# timer.net
KiCad netlist of a schematic drawn in EAGLE
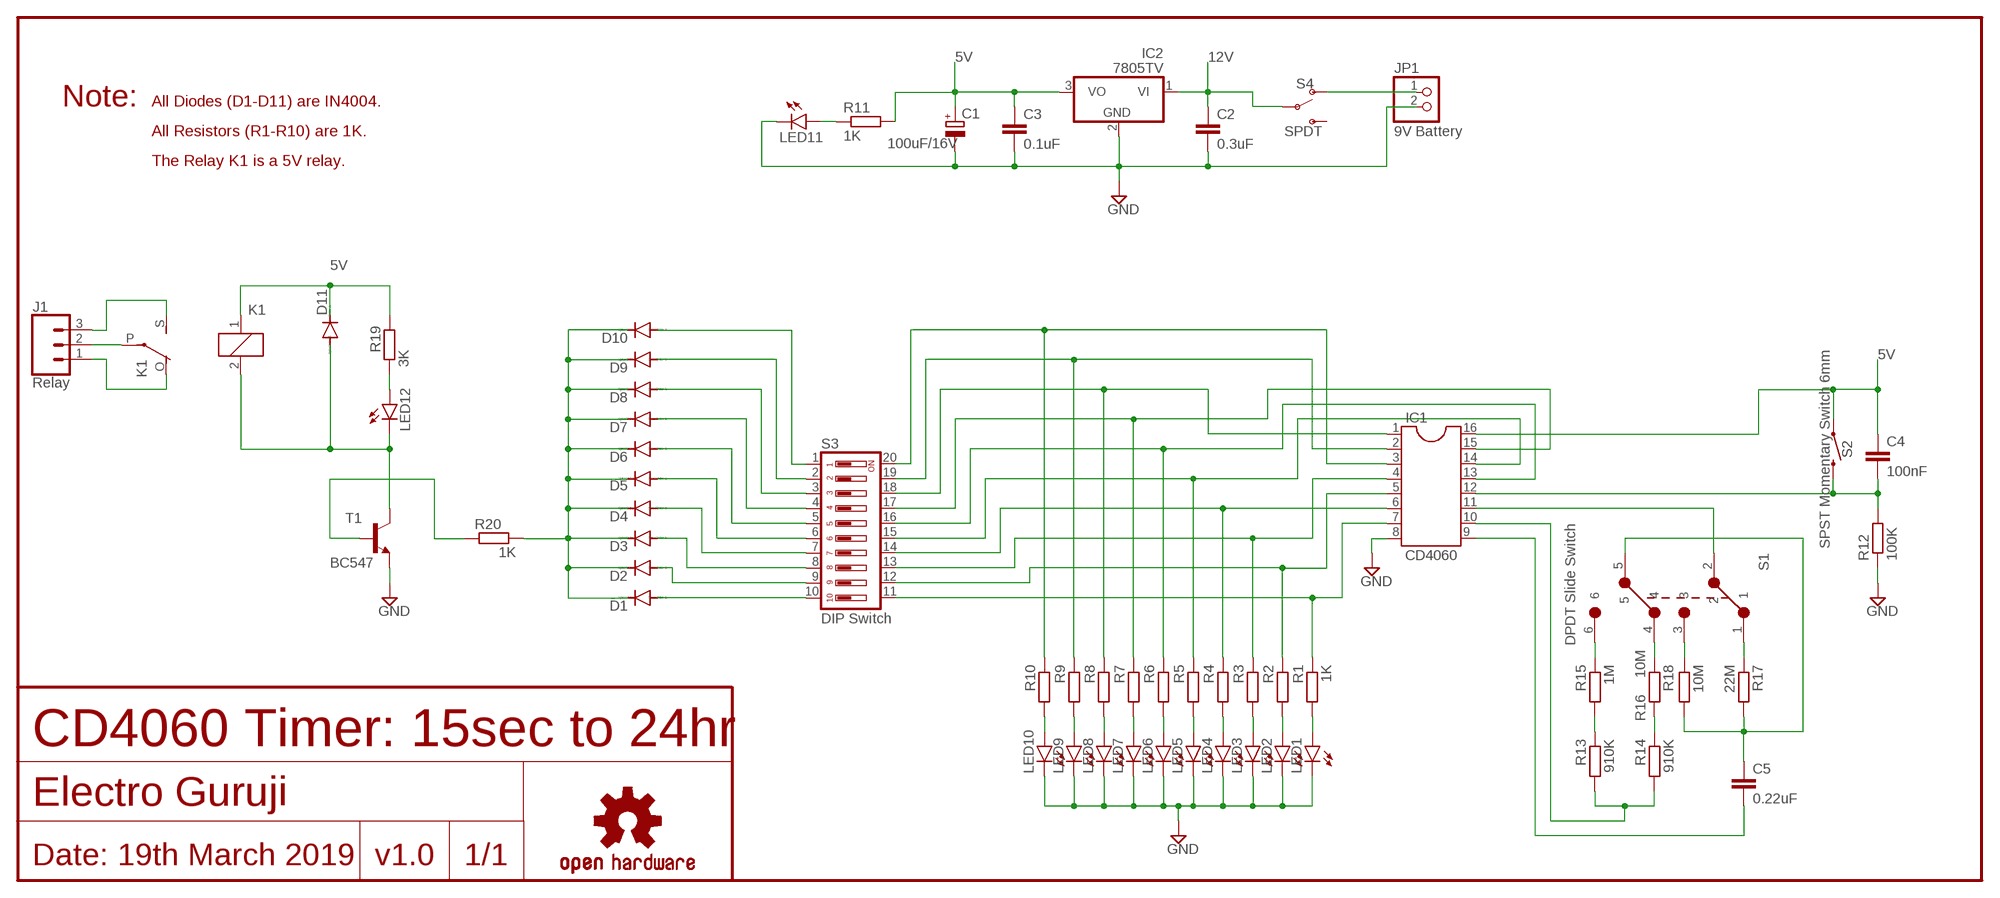
[diagram p0: schematic, sheet 1]

(export (version "E")
  (design (tool "Eeschema 10.0.6"))
  (components
    (comp (ref "C1")
      (value "100uF/16V")
      (footprint "eagle-import:E2,5-6")
      (libsource (lib "eagle-import") (part "CPOL-EUE2.5-6"))
    )
    (comp (ref "C2")
      (value "0.3uF")
      (footprint "eagle-import:C025-050X050")
      (libsource (lib "eagle-import") (part "C-EU025-050X050"))
    )
    (comp (ref "C3")
      (value "0.1uF")
      (footprint "eagle-import:C025-050X050")
      (libsource (lib "eagle-import") (part "C-EU025-050X050"))
    )
    (comp (ref "C4")
      (value "100nF")
      (footprint "eagle-import:C025-050X050")
      (libsource (lib "eagle-import") (part "C-EU025-050X050"))
    )
    (comp (ref "C5")
      (value "0.22uF")
      (footprint "eagle-import:C102-043X133")
      (libsource (lib "eagle-import") (part "C-EU102-043X133"))
    )
    (comp (ref "D1")
      (value "1N4004")
      (footprint "eagle-import:DO41-10")
      (libsource (lib "eagle-import") (part "1N4004"))
    )
    (comp (ref "D2")
      (value "1N4004")
      (footprint "eagle-import:DO41-10")
      (libsource (lib "eagle-import") (part "1N4004"))
    )
    (comp (ref "D3")
      (value "1N4004")
      (footprint "eagle-import:DO41-10")
      (libsource (lib "eagle-import") (part "1N4004"))
    )
    (comp (ref "D4")
      (value "1N4004")
      (footprint "eagle-import:DO41-10")
      (libsource (lib "eagle-import") (part "1N4004"))
    )
    (comp (ref "D5")
      (value "1N4004")
      (footprint "eagle-import:DO41-10")
      (libsource (lib "eagle-import") (part "1N4004"))
    )
    (comp (ref "D6")
      (value "1N4004")
      (footprint "eagle-import:DO41-10")
      (libsource (lib "eagle-import") (part "1N4004"))
    )
    (comp (ref "D7")
      (value "1N4004")
      (footprint "eagle-import:DO41-10")
      (libsource (lib "eagle-import") (part "1N4004"))
    )
    (comp (ref "D8")
      (value "1N4004")
      (footprint "eagle-import:DO41-10")
      (libsource (lib "eagle-import") (part "1N4004"))
    )
    (comp (ref "D9")
      (value "1N4004")
      (footprint "eagle-import:DO41-10")
      (libsource (lib "eagle-import") (part "1N4004"))
    )
    (comp (ref "D10")
      (value "1N4004")
      (footprint "eagle-import:DO41-10")
      (libsource (lib "eagle-import") (part "1N4004"))
    )
    (comp (ref "D11")
      (value "1N4004")
      (footprint "eagle-import:DO41-10")
      (libsource (lib "eagle-import") (part "1N4004"))
    )
    (comp (ref "IC1")
      (value "CD4060")
      (footprint "eagle-import:SOCKET-16")
      (libsource (lib "eagle-import") (part "DIL16S"))
    )
    (comp (ref "IC2")
      (value "7805TV")
      (footprint "eagle-import:TO220V")
      (libsource (lib "eagle-import") (part "78TV05"))
    )
    (comp (ref "J1")
      (value "Relay")
      (footprint "eagle-import:SCREWTERMINAL-5MM-3")
      (libsource (lib "eagle-import") (part "CONN_03-SCREW-5MM"))
    )
    (comp (ref "JP1")
      (value "9V Battery")
      (footprint "eagle-import:1X02")
      (libsource (lib "eagle-import") (part "PINHD-1X2"))
    )
    (comp (ref "K1")
      (value "5V")
      (footprint "eagle-import:ZF112")
      (libsource (lib "eagle-import") (part "ZF112"))
    )
    (comp (ref "LED1")
      (value "LED5MM")
      (footprint "eagle-import:LED5MM")
      (libsource (lib "eagle-import") (part "LED5MM"))
    )
    (comp (ref "LED2")
      (value "LED5MM")
      (footprint "eagle-import:LED5MM")
      (libsource (lib "eagle-import") (part "LED5MM"))
    )
    (comp (ref "LED3")
      (value "LED5MM")
      (footprint "eagle-import:LED5MM")
      (libsource (lib "eagle-import") (part "LED5MM"))
    )
    (comp (ref "LED4")
      (value "LED5MM")
      (footprint "eagle-import:LED5MM")
      (libsource (lib "eagle-import") (part "LED5MM"))
    )
    (comp (ref "LED5")
      (value "LED5MM")
      (footprint "eagle-import:LED5MM")
      (libsource (lib "eagle-import") (part "LED5MM"))
    )
    (comp (ref "LED6")
      (value "LED5MM")
      (footprint "eagle-import:LED5MM")
      (libsource (lib "eagle-import") (part "LED5MM"))
    )
    (comp (ref "LED7")
      (value "LED5MM")
      (footprint "eagle-import:LED5MM")
      (libsource (lib "eagle-import") (part "LED5MM"))
    )
    (comp (ref "LED8")
      (value "LED5MM")
      (footprint "eagle-import:LED5MM")
      (libsource (lib "eagle-import") (part "LED5MM"))
    )
    (comp (ref "LED9")
      (value "LED5MM")
      (footprint "eagle-import:LED5MM")
      (libsource (lib "eagle-import") (part "LED5MM"))
    )
    (comp (ref "LED10")
      (value "LED5MM")
      (footprint "eagle-import:LED5MM")
      (libsource (lib "eagle-import") (part "LED5MM"))
    )
    (comp (ref "LED11")
      (value "LED5MM")
      (footprint "eagle-import:LED5MM")
      (libsource (lib "eagle-import") (part "LED5MM"))
    )
    (comp (ref "LED12")
      (value "LED5MM")
      (footprint "eagle-import:LED5MM")
      (libsource (lib "eagle-import") (part "LED5MM"))
    )
    (comp (ref "LOGO1")
      (value "OSHW-LOGOS-COPPER")
      (footprint "eagle-import:OSHW-LOGO-S_COPPER")
      (libsource (lib "eagle-import") (part "OSHW-LOGOS-COPPER"))
    )
    (comp (ref "R1")
      (value "1K")
      (footprint "eagle-import:0207_10")
      (libsource (lib "eagle-import") (part "R-EU_0207/10"))
    )
    (comp (ref "R2")
      (value "R-EU_0207/10")
      (footprint "eagle-import:0207_10")
      (libsource (lib "eagle-import") (part "R-EU_0207/10"))
    )
    (comp (ref "R3")
      (value "R-EU_0207/10")
      (footprint "eagle-import:0207_10")
      (libsource (lib "eagle-import") (part "R-EU_0207/10"))
    )
    (comp (ref "R4")
      (value "R-EU_0207/10")
      (footprint "eagle-import:0207_10")
      (libsource (lib "eagle-import") (part "R-EU_0207/10"))
    )
    (comp (ref "R5")
      (value "R-EU_0207/10")
      (footprint "eagle-import:0207_10")
      (libsource (lib "eagle-import") (part "R-EU_0207/10"))
    )
    (comp (ref "R6")
      (value "R-EU_0207/10")
      (footprint "eagle-import:0207_10")
      (libsource (lib "eagle-import") (part "R-EU_0207/10"))
    )
    (comp (ref "R7")
      (value "R-EU_0207/10")
      (footprint "eagle-import:0207_10")
      (libsource (lib "eagle-import") (part "R-EU_0207/10"))
    )
    (comp (ref "R8")
      (value "R-EU_0207/10")
      (footprint "eagle-import:0207_10")
      (libsource (lib "eagle-import") (part "R-EU_0207/10"))
    )
    (comp (ref "R9")
      (value "R-EU_0207/10")
      (footprint "eagle-import:0207_10")
      (libsource (lib "eagle-import") (part "R-EU_0207/10"))
    )
    (comp (ref "R10")
      (value "R-EU_0207/10")
      (footprint "eagle-import:0207_10")
      (libsource (lib "eagle-import") (part "R-EU_0207/10"))
    )
    (comp (ref "R11")
      (value "1K")
      (footprint "eagle-import:0207_10")
      (libsource (lib "eagle-import") (part "R-EU_0207/10"))
    )
    (comp (ref "R12")
      (value "100K")
      (footprint "eagle-import:0207_10")
      (libsource (lib "eagle-import") (part "R-EU_0207/10"))
    )
    (comp (ref "R13")
      (value "910K")
      (footprint "eagle-import:0207_10")
      (libsource (lib "eagle-import") (part "R-EU_0207/10"))
    )
    (comp (ref "R14")
      (value "910K")
      (footprint "eagle-import:0207_10")
      (libsource (lib "eagle-import") (part "R-EU_0207/10"))
    )
    (comp (ref "R15")
      (value "1M")
      (footprint "eagle-import:0207_10")
      (libsource (lib "eagle-import") (part "R-EU_0207/10"))
    )
    (comp (ref "R16")
      (value "10M")
      (footprint "eagle-import:0207_10")
      (libsource (lib "eagle-import") (part "R-EU_0207/10"))
    )
    (comp (ref "R17")
      (value "22M")
      (footprint "eagle-import:0207_10")
      (libsource (lib "eagle-import") (part "R-EU_0207/10"))
    )
    (comp (ref "R18")
      (value "10M")
      (footprint "eagle-import:0207_10")
      (libsource (lib "eagle-import") (part "R-EU_0207/10"))
    )
    (comp (ref "R19")
      (value "3K")
      (footprint "eagle-import:0207_10")
      (libsource (lib "eagle-import") (part "R-EU_0207/10"))
    )
    (comp (ref "R20")
      (value "1K")
      (footprint "eagle-import:0207_10")
      (libsource (lib "eagle-import") (part "R-EU_0207/10"))
    )
    (comp (ref "S1")
      (value "DPDT Slide Switch")
      (footprint "eagle-import:DPDT_SEC")
      (libsource (lib "eagle-import") (part "DPDT_SEC"))
    )
    (comp (ref "S2")
      (value "SPST Momentary Switch 6mm")
      (footprint "eagle-import:TACTILE_SWITCH_PTH_6.0MM")
      (libsource (lib "eagle-import") (part "MOMENTARY-SWITCH-SPST-PTH-6.0MM"))
    )
    (comp (ref "S3")
      (value "DIP Switch")
      (footprint "eagle-import:DIP10YL")
      (libsource (lib "eagle-import") (part "DIP10YL"))
    )
    (comp (ref "S4")
      (value "SPDT")
      (footprint "eagle-import:SWITCH_SPDT_PTH_11.6X4.0MM")
      (libsource (lib "eagle-import") (part "SWITCH-SPDT-PTH-11.6X4.0MM"))
    )
    (comp (ref "T1")
      (value "BC547")
      (footprint "eagle-import:TO92-EBC")
      (libsource (lib "eagle-import") (part "-NPN-TO92-EBC"))
    )
  )
  (nets
    (net (code "1") (name "/5V") (class "Default")
      (node (ref "C1") (pin "+") (pinfunction "+_+") (pintype "passive"))
      (node (ref "C3") (pin "1") (pinfunction "1_1") (pintype "passive"))
      (node (ref "C4") (pin "1") (pinfunction "1_1") (pintype "passive"))
      (node (ref "D11") (pin "C") (pinfunction "C_C") (pintype "passive"))
      (node (ref "IC1") (pin "16") (pinfunction "16_16") (pintype "passive"))
      (node (ref "IC2") (pin "3") (pinfunction "VO_3") (pintype "passive"))
      (node (ref "K1") (pin "1") (pinfunction "1_1") (pintype "passive"))
      (node (ref "R11") (pin "2") (pinfunction "2_2") (pintype "passive"))
      (node (ref "R19") (pin "2") (pinfunction "2_2") (pintype "passive"))
      (node (ref "S2") (pin "1") (pinfunction "1_1") (pintype "passive"))
    )
    (net (code "2") (name "/12V") (class "Default")
      (node (ref "C2") (pin "1") (pinfunction "1_1") (pintype "passive"))
      (node (ref "IC2") (pin "1") (pinfunction "VI_1") (pintype "input"))
      (node (ref "S4") (pin "2") (pinfunction "P_2") (pintype "passive"))
    )
    (net (code "3") (name "GND") (class "Default")
      (node (ref "C1") (pin "-") (pinfunction "-_-") (pintype "passive"))
      (node (ref "C2") (pin "2") (pinfunction "2_2") (pintype "passive"))
      (node (ref "C3") (pin "2") (pinfunction "2_2") (pintype "passive"))
      (node (ref "IC1") (pin "8") (pinfunction "8_8") (pintype "passive"))
      (node (ref "IC2") (pin "2") (pinfunction "GND_2") (pintype "passive"))
      (node (ref "JP1") (pin "2") (pinfunction "2_2") (pintype "passive"))
      (node (ref "LED1") (pin "K") (pinfunction "C_K") (pintype "passive"))
      (node (ref "LED10") (pin "K") (pinfunction "C_K") (pintype "passive"))
      (node (ref "LED11") (pin "K") (pinfunction "C_K") (pintype "passive"))
      (node (ref "LED2") (pin "K") (pinfunction "C_K") (pintype "passive"))
      (node (ref "LED3") (pin "K") (pinfunction "C_K") (pintype "passive"))
      (node (ref "LED4") (pin "K") (pinfunction "C_K") (pintype "passive"))
      (node (ref "LED5") (pin "K") (pinfunction "C_K") (pintype "passive"))
      (node (ref "LED6") (pin "K") (pinfunction "C_K") (pintype "passive"))
      (node (ref "LED7") (pin "K") (pinfunction "C_K") (pintype "passive"))
      (node (ref "LED8") (pin "K") (pinfunction "C_K") (pintype "passive"))
      (node (ref "LED9") (pin "K") (pinfunction "C_K") (pintype "passive"))
      (node (ref "R12") (pin "1") (pinfunction "1_1") (pintype "passive"))
      (node (ref "T1") (pin "E") (pinfunction "E_E") (pintype "passive"))
    )
    (net (code "4") (name "Net-(C5-Pad1)") (class "Default")
      (node (ref "C5") (pin "1") (pinfunction "1_1") (pintype "passive"))
      (node (ref "R17") (pin "2") (pinfunction "2_2") (pintype "passive"))
      (node (ref "R18") (pin "2") (pinfunction "2_2") (pintype "passive"))
      (node (ref "S1") (pin "5") (pinfunction "5_5") (pintype "bidirectional"))
    )
    (net (code "5") (name "Net-(C5-Pad2)") (class "Default")
      (node (ref "C5") (pin "2") (pinfunction "2_2") (pintype "passive"))
      (node (ref "IC1") (pin "9") (pinfunction "9_9") (pintype "passive"))
    )
    (net (code "6") (name "Net-(D1-PadA)") (class "Default")
      (node (ref "D1") (pin "A") (pinfunction "A_A") (pintype "passive"))
      (node (ref "S3") (pin "10") (pinfunction "10_10") (pintype "passive"))
    )
    (net (code "7") (name "Net-(D1-PadC)") (class "Default")
      (node (ref "D1") (pin "C") (pinfunction "C_C") (pintype "passive"))
      (node (ref "D10") (pin "C") (pinfunction "C_C") (pintype "passive"))
      (node (ref "D2") (pin "C") (pinfunction "C_C") (pintype "passive"))
      (node (ref "D3") (pin "C") (pinfunction "C_C") (pintype "passive"))
      (node (ref "D4") (pin "C") (pinfunction "C_C") (pintype "passive"))
      (node (ref "D5") (pin "C") (pinfunction "C_C") (pintype "passive"))
      (node (ref "D6") (pin "C") (pinfunction "C_C") (pintype "passive"))
      (node (ref "D7") (pin "C") (pinfunction "C_C") (pintype "passive"))
      (node (ref "D8") (pin "C") (pinfunction "C_C") (pintype "passive"))
      (node (ref "D9") (pin "C") (pinfunction "C_C") (pintype "passive"))
      (node (ref "R20") (pin "1") (pinfunction "1_1") (pintype "passive"))
    )
    (net (code "8") (name "Net-(D2-PadA)") (class "Default")
      (node (ref "D2") (pin "A") (pinfunction "A_A") (pintype "passive"))
      (node (ref "S3") (pin "9") (pinfunction "9_9") (pintype "passive"))
    )
    (net (code "9") (name "Net-(D3-PadA)") (class "Default")
      (node (ref "D3") (pin "A") (pinfunction "A_A") (pintype "passive"))
      (node (ref "S3") (pin "8") (pinfunction "8_8") (pintype "passive"))
    )
    (net (code "10") (name "Net-(D4-PadA)") (class "Default")
      (node (ref "D4") (pin "A") (pinfunction "A_A") (pintype "passive"))
      (node (ref "S3") (pin "7") (pinfunction "7_7") (pintype "passive"))
    )
    (net (code "11") (name "Net-(D5-PadA)") (class "Default")
      (node (ref "D5") (pin "A") (pinfunction "A_A") (pintype "passive"))
      (node (ref "S3") (pin "6") (pinfunction "6_6") (pintype "passive"))
    )
    (net (code "12") (name "Net-(D6-PadA)") (class "Default")
      (node (ref "D6") (pin "A") (pinfunction "A_A") (pintype "passive"))
      (node (ref "S3") (pin "5") (pinfunction "5_5") (pintype "passive"))
    )
    (net (code "13") (name "Net-(D7-PadA)") (class "Default")
      (node (ref "D7") (pin "A") (pinfunction "A_A") (pintype "passive"))
      (node (ref "S3") (pin "4") (pinfunction "4_4") (pintype "passive"))
    )
    (net (code "14") (name "Net-(D8-PadA)") (class "Default")
      (node (ref "D8") (pin "A") (pinfunction "A_A") (pintype "passive"))
      (node (ref "S3") (pin "3") (pinfunction "3_3") (pintype "passive"))
    )
    (net (code "15") (name "Net-(D9-PadA)") (class "Default")
      (node (ref "D9") (pin "A") (pinfunction "A_A") (pintype "passive"))
      (node (ref "S3") (pin "2") (pinfunction "2_2") (pintype "passive"))
    )
    (net (code "16") (name "Net-(D10-PadA)") (class "Default")
      (node (ref "D10") (pin "A") (pinfunction "A_A") (pintype "passive"))
      (node (ref "S3") (pin "1") (pinfunction "1_1") (pintype "passive"))
    )
    (net (code "17") (name "Net-(IC1-Pad1)") (class "Default")
      (node (ref "IC1") (pin "1") (pinfunction "1_1") (pintype "passive"))
      (node (ref "R8") (pin "1") (pinfunction "1_1") (pintype "passive"))
      (node (ref "S3") (pin "18") (pinfunction "18_18") (pintype "passive"))
    )
    (net (code "18") (name "Net-(IC1-Pad2)") (class "Default")
      (node (ref "IC1") (pin "2") (pinfunction "2_2") (pintype "passive"))
      (node (ref "R9") (pin "1") (pinfunction "1_1") (pintype "passive"))
      (node (ref "S3") (pin "19") (pinfunction "19_19") (pintype "passive"))
    )
    (net (code "19") (name "Net-(IC1-Pad3)") (class "Default")
      (node (ref "IC1") (pin "3") (pinfunction "3_3") (pintype "passive"))
      (node (ref "R10") (pin "1") (pinfunction "1_1") (pintype "passive"))
      (node (ref "S3") (pin "20") (pinfunction "20_20") (pintype "passive"))
    )
    (net (code "20") (name "Net-(IC1-Pad4)") (class "Default")
      (node (ref "IC1") (pin "4") (pinfunction "4_4") (pintype "passive"))
      (node (ref "R3") (pin "1") (pinfunction "1_1") (pintype "passive"))
      (node (ref "S3") (pin "13") (pinfunction "13_13") (pintype "passive"))
    )
    (net (code "21") (name "Net-(IC1-Pad5)") (class "Default")
      (node (ref "IC1") (pin "5") (pinfunction "5_5") (pintype "passive"))
      (node (ref "R2") (pin "1") (pinfunction "1_1") (pintype "passive"))
      (node (ref "S3") (pin "12") (pinfunction "12_12") (pintype "passive"))
    )
    (net (code "22") (name "Net-(IC1-Pad6)") (class "Default")
      (node (ref "IC1") (pin "6") (pinfunction "6_6") (pintype "passive"))
      (node (ref "R4") (pin "1") (pinfunction "1_1") (pintype "passive"))
      (node (ref "S3") (pin "14") (pinfunction "14_14") (pintype "passive"))
    )
    (net (code "23") (name "Net-(IC1-Pad7)") (class "Default")
      (node (ref "IC1") (pin "7") (pinfunction "7_7") (pintype "passive"))
      (node (ref "R1") (pin "1") (pinfunction "1_1") (pintype "passive"))
      (node (ref "S3") (pin "11") (pinfunction "11_11") (pintype "passive"))
    )
    (net (code "24") (name "Net-(IC1-Pad10)") (class "Default")
      (node (ref "IC1") (pin "10") (pinfunction "10_10") (pintype "passive"))
      (node (ref "R13") (pin "2") (pinfunction "2_2") (pintype "passive"))
      (node (ref "R14") (pin "2") (pinfunction "2_2") (pintype "passive"))
    )
    (net (code "25") (name "Net-(IC1-Pad11)") (class "Default")
      (node (ref "IC1") (pin "11") (pinfunction "11_11") (pintype "passive"))
      (node (ref "S1") (pin "2") (pinfunction "2_2") (pintype "bidirectional"))
    )
    (net (code "26") (name "Net-(IC1-Pad13)") (class "Default")
      (node (ref "IC1") (pin "13") (pinfunction "13_13") (pintype "passive"))
      (node (ref "R6") (pin "1") (pinfunction "1_1") (pintype "passive"))
      (node (ref "S3") (pin "16") (pinfunction "16_16") (pintype "passive"))
    )
    (net (code "27") (name "Net-(IC1-Pad14)") (class "Default")
      (node (ref "IC1") (pin "14") (pinfunction "14_14") (pintype "passive"))
      (node (ref "R5") (pin "1") (pinfunction "1_1") (pintype "passive"))
      (node (ref "S3") (pin "15") (pinfunction "15_15") (pintype "passive"))
    )
    (net (code "28") (name "Net-(IC1-Pad15)") (class "Default")
      (node (ref "IC1") (pin "15") (pinfunction "15_15") (pintype "passive"))
      (node (ref "R7") (pin "1") (pinfunction "1_1") (pintype "passive"))
      (node (ref "S3") (pin "17") (pinfunction "17_17") (pintype "passive"))
    )
    (net (code "29") (name "Net-(J1-Pad1)") (class "Default")
      (node (ref "J1") (pin "1") (pinfunction "1_1") (pintype "passive"))
      (node (ref "K1") (pin "O") (pinfunction "O_O") (pintype "passive"))
    )
    (net (code "30") (name "Net-(J1-Pad2)") (class "Default")
      (node (ref "J1") (pin "2") (pinfunction "2_2") (pintype "passive"))
      (node (ref "K1") (pin "P") (pinfunction "P_P") (pintype "passive"))
    )
    (net (code "31") (name "Net-(J1-Pad3)") (class "Default")
      (node (ref "J1") (pin "3") (pinfunction "3_3") (pintype "passive"))
      (node (ref "K1") (pin "S") (pinfunction "S_S") (pintype "passive"))
    )
    (net (code "32") (name "Net-(LED1-PadA)") (class "Default")
      (node (ref "LED1") (pin "A") (pinfunction "A_A") (pintype "passive"))
      (node (ref "R1") (pin "2") (pinfunction "2_2") (pintype "passive"))
    )
    (net (code "33") (name "Net-(LED2-PadA)") (class "Default")
      (node (ref "LED2") (pin "A") (pinfunction "A_A") (pintype "passive"))
      (node (ref "R2") (pin "2") (pinfunction "2_2") (pintype "passive"))
    )
    (net (code "34") (name "Net-(LED3-PadA)") (class "Default")
      (node (ref "LED3") (pin "A") (pinfunction "A_A") (pintype "passive"))
      (node (ref "R3") (pin "2") (pinfunction "2_2") (pintype "passive"))
    )
    (net (code "35") (name "Net-(LED4-PadA)") (class "Default")
      (node (ref "LED4") (pin "A") (pinfunction "A_A") (pintype "passive"))
      (node (ref "R4") (pin "2") (pinfunction "2_2") (pintype "passive"))
    )
    (net (code "36") (name "Net-(LED5-PadA)") (class "Default")
      (node (ref "LED5") (pin "A") (pinfunction "A_A") (pintype "passive"))
      (node (ref "R5") (pin "2") (pinfunction "2_2") (pintype "passive"))
    )
    (net (code "37") (name "Net-(LED6-PadA)") (class "Default")
      (node (ref "LED6") (pin "A") (pinfunction "A_A") (pintype "passive"))
      (node (ref "R6") (pin "2") (pinfunction "2_2") (pintype "passive"))
    )
    (net (code "38") (name "Net-(LED7-PadA)") (class "Default")
      (node (ref "LED7") (pin "A") (pinfunction "A_A") (pintype "passive"))
      (node (ref "R7") (pin "2") (pinfunction "2_2") (pintype "passive"))
    )
    (net (code "39") (name "Net-(LED8-PadA)") (class "Default")
      (node (ref "LED8") (pin "A") (pinfunction "A_A") (pintype "passive"))
      (node (ref "R8") (pin "2") (pinfunction "2_2") (pintype "passive"))
    )
    (net (code "40") (name "Net-(LED9-PadA)") (class "Default")
      (node (ref "LED9") (pin "A") (pinfunction "A_A") (pintype "passive"))
      (node (ref "R9") (pin "2") (pinfunction "2_2") (pintype "passive"))
    )
    (net (code "41") (name "Net-(LED10-PadA)") (class "Default")
      (node (ref "LED10") (pin "A") (pinfunction "A_A") (pintype "passive"))
      (node (ref "R10") (pin "2") (pinfunction "2_2") (pintype "passive"))
    )
    (net (code "42") (name "Net-(LED11-PadA)") (class "Default")
      (node (ref "LED11") (pin "A") (pinfunction "A_A") (pintype "passive"))
      (node (ref "R11") (pin "1") (pinfunction "1_1") (pintype "passive"))
    )
    (net (code "43") (name "Net-(LED12-C)") (class "Default")
      (node (ref "D11") (pin "A") (pinfunction "A_A") (pintype "passive"))
      (node (ref "K1") (pin "2") (pinfunction "2_2") (pintype "passive"))
      (node (ref "LED12") (pin "K") (pinfunction "C_K") (pintype "passive"))
      (node (ref "T1") (pin "C") (pinfunction "C_C") (pintype "passive"))
    )
    (net (code "44") (name "Net-(LED12-PadA)") (class "Default")
      (node (ref "LED12") (pin "A") (pinfunction "A_A") (pintype "passive"))
      (node (ref "R19") (pin "1") (pinfunction "1_1") (pintype "passive"))
    )
    (net (code "45") (name "Net-(R13-Pad1)") (class "Default")
      (node (ref "R13") (pin "1") (pinfunction "1_1") (pintype "passive"))
      (node (ref "R15") (pin "2") (pinfunction "2_2") (pintype "passive"))
    )
    (net (code "46") (name "Net-(R14-Pad1)") (class "Default")
      (node (ref "R14") (pin "1") (pinfunction "1_1") (pintype "passive"))
      (node (ref "R16") (pin "2") (pinfunction "2_2") (pintype "passive"))
    )
    (net (code "47") (name "Net-(R15-Pad1)") (class "Default")
      (node (ref "R15") (pin "1") (pinfunction "1_1") (pintype "passive"))
      (node (ref "S1") (pin "6") (pinfunction "6_6") (pintype "bidirectional"))
    )
    (net (code "48") (name "Net-(R16-Pad1)") (class "Default")
      (node (ref "R16") (pin "1") (pinfunction "1_1") (pintype "passive"))
      (node (ref "S1") (pin "4") (pinfunction "4_4") (pintype "bidirectional"))
    )
    (net (code "49") (name "Net-(R17-Pad1)") (class "Default")
      (node (ref "R17") (pin "1") (pinfunction "1_1") (pintype "passive"))
      (node (ref "S1") (pin "1") (pinfunction "1_1") (pintype "bidirectional"))
    )
    (net (code "50") (name "Net-(R18-Pad1)") (class "Default")
      (node (ref "R18") (pin "1") (pinfunction "1_1") (pintype "passive"))
      (node (ref "S1") (pin "3") (pinfunction "3_3") (pintype "bidirectional"))
    )
    (net (code "51") (name "Net-(R20-Pad2)") (class "Default")
      (node (ref "R20") (pin "2") (pinfunction "2_2") (pintype "passive"))
      (node (ref "T1") (pin "B") (pinfunction "B_B") (pintype "passive"))
    )
    (net (code "52") (name "Net-(S2-2)") (class "Default")
      (node (ref "C4") (pin "2") (pinfunction "2_2") (pintype "passive"))
      (node (ref "IC1") (pin "12") (pinfunction "12_12") (pintype "passive"))
      (node (ref "R12") (pin "2") (pinfunction "2_2") (pintype "passive"))
      (node (ref "S2") (pin "3") (pinfunction "2_3") (pintype "passive"))
    )
    (net (code "53") (name "Net-(S4-O)") (class "Default")
      (node (ref "JP1") (pin "1") (pinfunction "1_1") (pintype "passive"))
      (node (ref "S4") (pin "1") (pinfunction "O_1") (pintype "passive"))
    )
    (net (code "54") (name "unconnected-(S4-S-Pad3)") (class "Default")
      (node (ref "S4") (pin "3") (pinfunction "S_3") (pintype "passive"))
    )
  )
)
